# midi-switcher.net
KiCad netlist of a schematic drawn in EAGLE
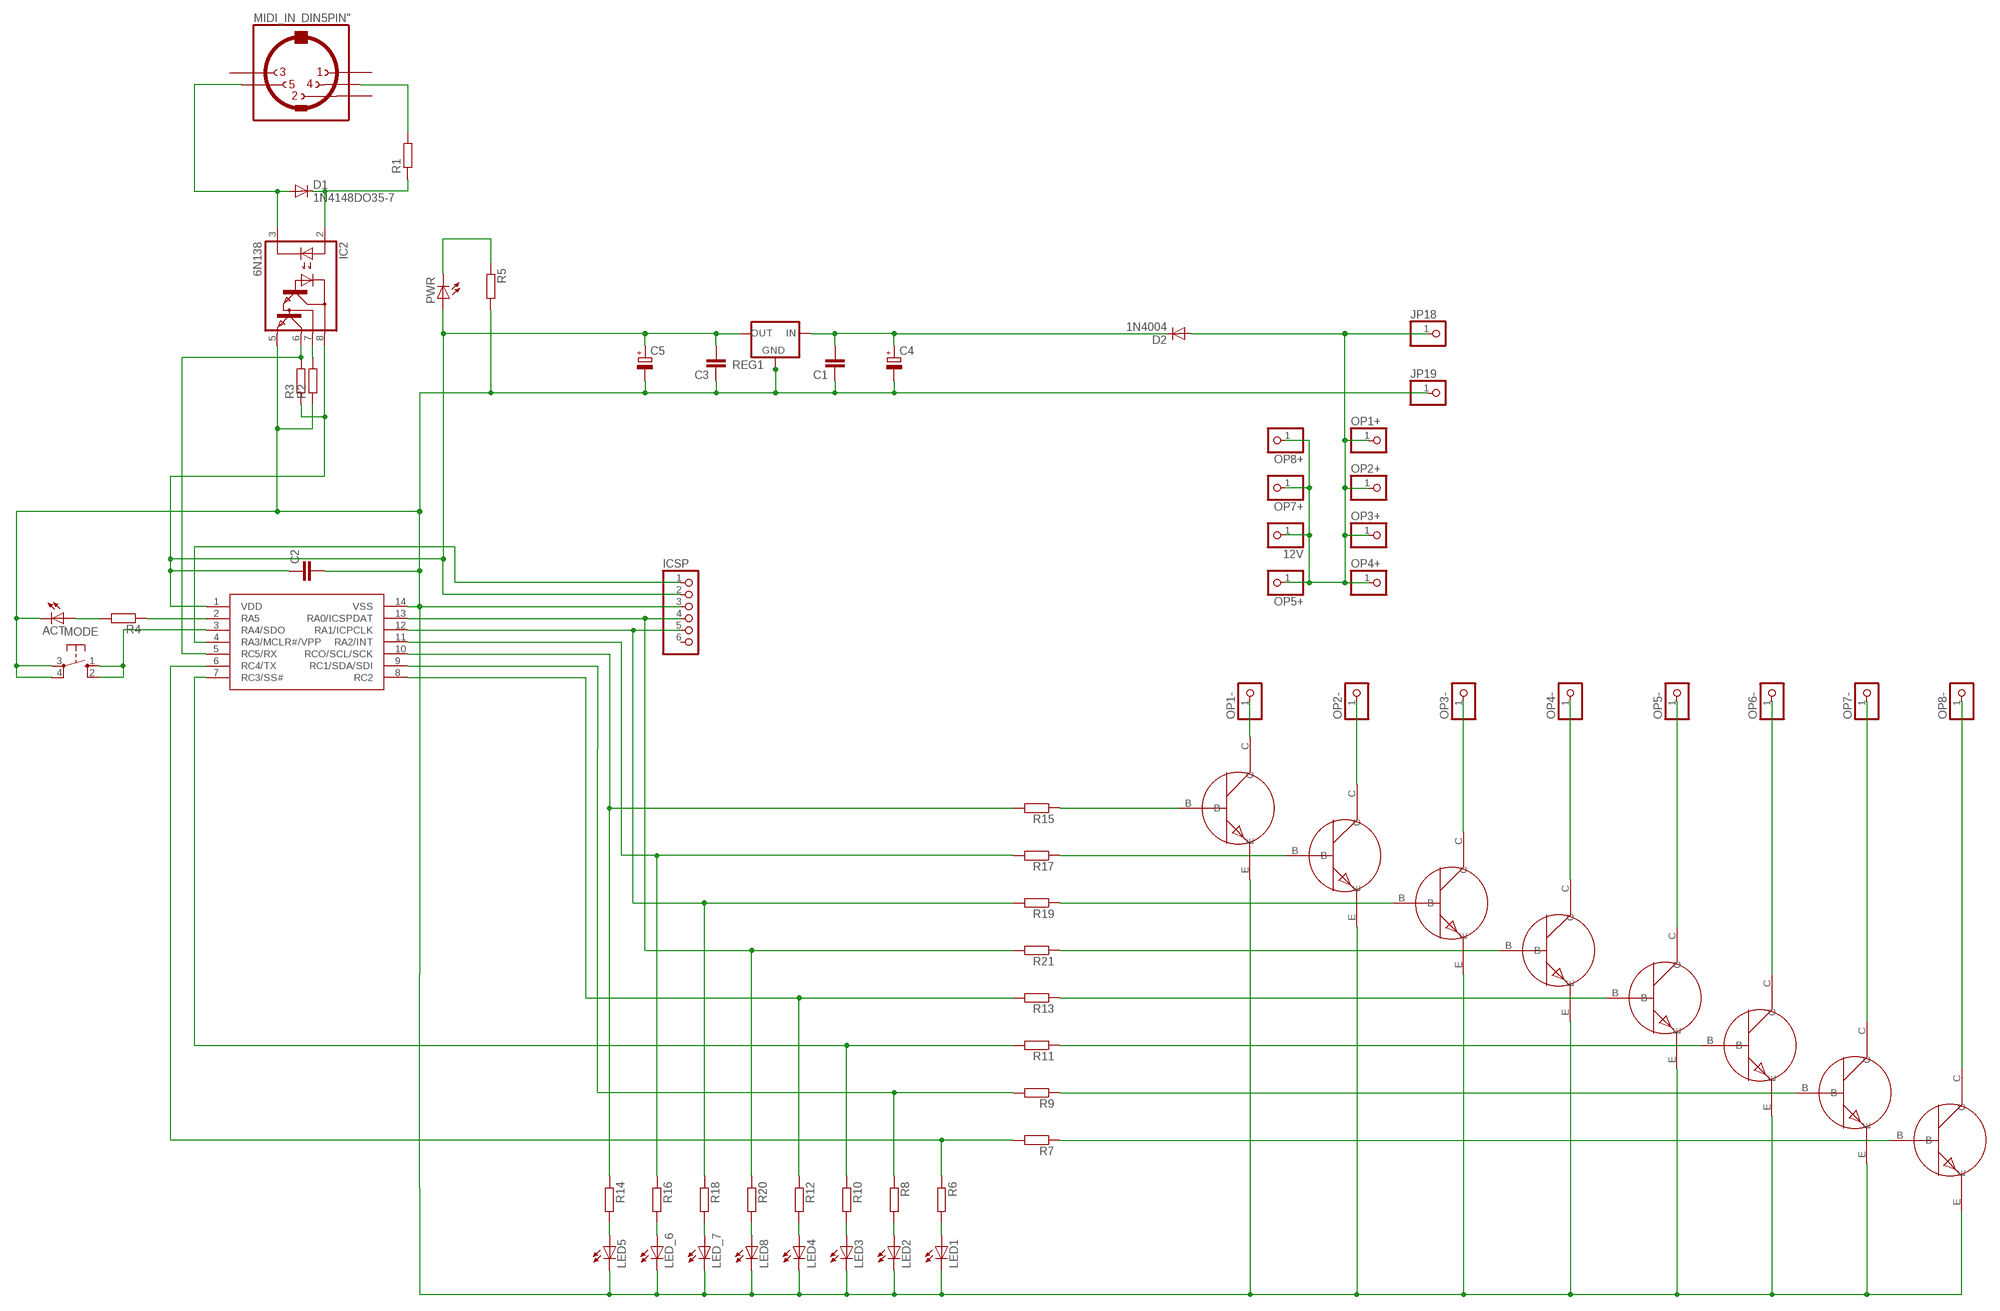
[diagram p0: schematic, sheet 1]

(export (version "E")
  (design (tool "Eeschema 10.0.6"))
  (components
    (comp (ref "12V")
      (value "PINHD-1X1")
      (footprint "eagle-import:1X01")
      (libsource (lib "eagle-import") (part "PINHD-1X1"))
    )
    (comp (ref "ACT")
      (value "LED3MM")
      (footprint "eagle-import:LED3MM")
      (libsource (lib "eagle-import") (part "LED3MM"))
    )
    (comp (ref "C1")
      (value "C-EU025-025X050")
      (footprint "eagle-import:C025-025X050")
      (libsource (lib "eagle-import") (part "C-EU025-025X050"))
    )
    (comp (ref "C2")
      (value "C-EU025-025X050")
      (footprint "eagle-import:C025-025X050")
      (libsource (lib "eagle-import") (part "C-EU025-025X050"))
    )
    (comp (ref "C3")
      (value "C-EU025-025X050")
      (footprint "eagle-import:C025-025X050")
      (libsource (lib "eagle-import") (part "C-EU025-025X050"))
    )
    (comp (ref "C4")
      (value "CPOL-EUE2.5-7")
      (footprint "eagle-import:E2,5-7")
      (libsource (lib "eagle-import") (part "CPOL-EUE2.5-7"))
    )
    (comp (ref "C5")
      (value "CPOL-EUE2.5-7")
      (footprint "eagle-import:E2,5-7")
      (libsource (lib "eagle-import") (part "CPOL-EUE2.5-7"))
    )
    (comp (ref "D1")
      (value "1N4148DO35-7")
      (footprint "eagle-import:DO35-7")
      (libsource (lib "eagle-import") (part "1N4148DO35-7"))
    )
    (comp (ref "D2")
      (value "1N4004")
      (footprint "eagle-import:DO41-10")
      (libsource (lib "eagle-import") (part "1N4004"))
    )
    (comp (ref "IC1")
      (value "PIC16F1825DIL14")
      (footprint "eagle-import:DIL14")
      (libsource (lib "eagle-import") (part "PIC16F1825DIL14"))
    )
    (comp (ref "IC2")
      (value "6N138")
      (footprint "eagle-import:DIL08")
      (libsource (lib "eagle-import") (part "6N138"))
    )
    (comp (ref "ICSP")
      (value "HEADER-1X6")
      (footprint "eagle-import:1X06_OVAL")
      (libsource (lib "eagle-import") (part "HEADER-1X6"))
    )
    (comp (ref "JP18")
      (value "PINHD-1X1")
      (footprint "eagle-import:1X01")
      (libsource (lib "eagle-import") (part "PINHD-1X1"))
    )
    (comp (ref "JP19")
      (value "PINHD-1X1")
      (footprint "eagle-import:1X01")
      (libsource (lib "eagle-import") (part "PINHD-1X1"))
    )
    (comp (ref "LED1")
      (value "LED3MM")
      (footprint "eagle-import:LED3MM")
      (libsource (lib "eagle-import") (part "LED3MM"))
    )
    (comp (ref "LED2")
      (value "LED3MM")
      (footprint "eagle-import:LED3MM")
      (libsource (lib "eagle-import") (part "LED3MM"))
    )
    (comp (ref "LED3")
      (value "LED3MM")
      (footprint "eagle-import:LED3MM")
      (libsource (lib "eagle-import") (part "LED3MM"))
    )
    (comp (ref "LED4")
      (value "LED3MM")
      (footprint "eagle-import:LED3MM")
      (libsource (lib "eagle-import") (part "LED3MM"))
    )
    (comp (ref "LED5")
      (value "LED3MM")
      (footprint "eagle-import:LED3MM")
      (libsource (lib "eagle-import") (part "LED3MM"))
    )
    (comp (ref "LED8")
      (value "LED3MM")
      (footprint "eagle-import:LED3MM")
      (libsource (lib "eagle-import") (part "LED3MM"))
    )
    (comp (ref "LED_6")
      (value "LED3MM")
      (footprint "eagle-import:LED3MM")
      (libsource (lib "eagle-import") (part "LED3MM"))
    )
    (comp (ref "LED_7")
      (value "LED3MM")
      (footprint "eagle-import:LED3MM")
      (libsource (lib "eagle-import") (part "LED3MM"))
    )
    (comp (ref "MIDI_IN")
      (value "DIN5PIN\"")
      (footprint "eagle-import:TRUCONN90")
      (libsource (lib "eagle-import") (part "DIN5PIN{dblquote}"))
    )
    (comp (ref "MODE")
      (value "10-XX")
      (footprint "eagle-import:B3F-10XX")
      (libsource (lib "eagle-import") (part "10-XX"))
    )
    (comp (ref "OP1+")
      (value "PINHD-1X1")
      (footprint "eagle-import:1X01")
      (libsource (lib "eagle-import") (part "PINHD-1X1"))
    )
    (comp (ref "OP1-")
      (value "PINHD-1X1")
      (footprint "eagle-import:1X01")
      (libsource (lib "eagle-import") (part "PINHD-1X1"))
    )
    (comp (ref "OP2+")
      (value "PINHD-1X1")
      (footprint "eagle-import:1X01")
      (libsource (lib "eagle-import") (part "PINHD-1X1"))
    )
    (comp (ref "OP2-")
      (value "PINHD-1X1")
      (footprint "eagle-import:1X01")
      (libsource (lib "eagle-import") (part "PINHD-1X1"))
    )
    (comp (ref "OP3+")
      (value "PINHD-1X1")
      (footprint "eagle-import:1X01")
      (libsource (lib "eagle-import") (part "PINHD-1X1"))
    )
    (comp (ref "OP3-")
      (value "PINHD-1X1")
      (footprint "eagle-import:1X01")
      (libsource (lib "eagle-import") (part "PINHD-1X1"))
    )
    (comp (ref "OP4+")
      (value "PINHD-1X1")
      (footprint "eagle-import:1X01")
      (libsource (lib "eagle-import") (part "PINHD-1X1"))
    )
    (comp (ref "OP4-")
      (value "PINHD-1X1")
      (footprint "eagle-import:1X01")
      (libsource (lib "eagle-import") (part "PINHD-1X1"))
    )
    (comp (ref "OP5+")
      (value "PINHD-1X1")
      (footprint "eagle-import:1X01")
      (libsource (lib "eagle-import") (part "PINHD-1X1"))
    )
    (comp (ref "OP5-")
      (value "PINHD-1X1")
      (footprint "eagle-import:1X01")
      (libsource (lib "eagle-import") (part "PINHD-1X1"))
    )
    (comp (ref "OP6-")
      (value "PINHD-1X1")
      (footprint "eagle-import:1X01")
      (libsource (lib "eagle-import") (part "PINHD-1X1"))
    )
    (comp (ref "OP7+")
      (value "PINHD-1X1")
      (footprint "eagle-import:1X01")
      (libsource (lib "eagle-import") (part "PINHD-1X1"))
    )
    (comp (ref "OP7-")
      (value "PINHD-1X1")
      (footprint "eagle-import:1X01")
      (libsource (lib "eagle-import") (part "PINHD-1X1"))
    )
    (comp (ref "OP8+")
      (value "PINHD-1X1")
      (footprint "eagle-import:1X01")
      (libsource (lib "eagle-import") (part "PINHD-1X1"))
    )
    (comp (ref "OP8-")
      (value "PINHD-1X1")
      (footprint "eagle-import:1X01")
      (libsource (lib "eagle-import") (part "PINHD-1X1"))
    )
    (comp (ref "PWR")
      (value "LED3MM")
      (footprint "eagle-import:LED3MM")
      (libsource (lib "eagle-import") (part "LED3MM"))
    )
    (comp (ref "R1")
      (value "R-EU_0207/7")
      (footprint "eagle-import:0207_7")
      (libsource (lib "eagle-import") (part "R-EU_0207/7"))
    )
    (comp (ref "R2")
      (value "R-EU_0207/7")
      (footprint "eagle-import:0207_7")
      (libsource (lib "eagle-import") (part "R-EU_0207/7"))
    )
    (comp (ref "R3")
      (value "R-EU_0207/7")
      (footprint "eagle-import:0207_7")
      (libsource (lib "eagle-import") (part "R-EU_0207/7"))
    )
    (comp (ref "R4")
      (value "R-EU_0207/7")
      (footprint "eagle-import:0207_7")
      (libsource (lib "eagle-import") (part "R-EU_0207/7"))
    )
    (comp (ref "R5")
      (value "R-EU_0207/7")
      (footprint "eagle-import:0207_7")
      (libsource (lib "eagle-import") (part "R-EU_0207/7"))
    )
    (comp (ref "R6")
      (value "R-EU_0207/7")
      (footprint "eagle-import:0207_7")
      (libsource (lib "eagle-import") (part "R-EU_0207/7"))
    )
    (comp (ref "R7")
      (value "R-EU_0207/7")
      (footprint "eagle-import:0207_7")
      (libsource (lib "eagle-import") (part "R-EU_0207/7"))
    )
    (comp (ref "R8")
      (value "R-EU_0207/7")
      (footprint "eagle-import:0207_7")
      (libsource (lib "eagle-import") (part "R-EU_0207/7"))
    )
    (comp (ref "R9")
      (value "R-EU_0207/7")
      (footprint "eagle-import:0207_7")
      (libsource (lib "eagle-import") (part "R-EU_0207/7"))
    )
    (comp (ref "R10")
      (value "R-EU_0207/7")
      (footprint "eagle-import:0207_7")
      (libsource (lib "eagle-import") (part "R-EU_0207/7"))
    )
    (comp (ref "R11")
      (value "R-EU_0207/7")
      (footprint "eagle-import:0207_7")
      (libsource (lib "eagle-import") (part "R-EU_0207/7"))
    )
    (comp (ref "R12")
      (value "R-EU_0207/7")
      (footprint "eagle-import:0207_7")
      (libsource (lib "eagle-import") (part "R-EU_0207/7"))
    )
    (comp (ref "R13")
      (value "R-EU_0207/7")
      (footprint "eagle-import:0207_7")
      (libsource (lib "eagle-import") (part "R-EU_0207/7"))
    )
    (comp (ref "R14")
      (value "R-EU_0207/7")
      (footprint "eagle-import:0207_7")
      (libsource (lib "eagle-import") (part "R-EU_0207/7"))
    )
    (comp (ref "R15")
      (value "R-EU_0207/7")
      (footprint "eagle-import:0207_7")
      (libsource (lib "eagle-import") (part "R-EU_0207/7"))
    )
    (comp (ref "R16")
      (value "R-EU_0207/7")
      (footprint "eagle-import:0207_7")
      (libsource (lib "eagle-import") (part "R-EU_0207/7"))
    )
    (comp (ref "R17")
      (value "R-EU_0207/7")
      (footprint "eagle-import:0207_7")
      (libsource (lib "eagle-import") (part "R-EU_0207/7"))
    )
    (comp (ref "R18")
      (value "R-EU_0207/7")
      (footprint "eagle-import:0207_7")
      (libsource (lib "eagle-import") (part "R-EU_0207/7"))
    )
    (comp (ref "R19")
      (value "R-EU_0207/7")
      (footprint "eagle-import:0207_7")
      (libsource (lib "eagle-import") (part "R-EU_0207/7"))
    )
    (comp (ref "R20")
      (value "R-EU_0207/7")
      (footprint "eagle-import:0207_7")
      (libsource (lib "eagle-import") (part "R-EU_0207/7"))
    )
    (comp (ref "R21")
      (value "R-EU_0207/7")
      (footprint "eagle-import:0207_7")
      (libsource (lib "eagle-import") (part "R-EU_0207/7"))
    )
    (comp (ref "REG1")
      (value "78XXS")
      (footprint "eagle-import:78XXS")
      (libsource (lib "eagle-import") (part "78XXS"))
    )
    (comp (ref "U$1")
      (value "TIP120")
      (footprint "eagle-import:TIP120")
      (libsource (lib "eagle-import") (part "TIP120"))
    )
    (comp (ref "U$2")
      (value "TIP120")
      (footprint "eagle-import:TIP120")
      (libsource (lib "eagle-import") (part "TIP120"))
    )
    (comp (ref "U$3")
      (value "TIP120")
      (footprint "eagle-import:TIP120")
      (libsource (lib "eagle-import") (part "TIP120"))
    )
    (comp (ref "U$4")
      (value "TIP120")
      (footprint "eagle-import:TIP120")
      (libsource (lib "eagle-import") (part "TIP120"))
    )
    (comp (ref "U$5")
      (value "TIP120")
      (footprint "eagle-import:TIP120")
      (libsource (lib "eagle-import") (part "TIP120"))
    )
    (comp (ref "U$6")
      (value "TIP120")
      (footprint "eagle-import:TIP120")
      (libsource (lib "eagle-import") (part "TIP120"))
    )
    (comp (ref "U$7")
      (value "TIP120")
      (footprint "eagle-import:TIP120")
      (libsource (lib "eagle-import") (part "TIP120"))
    )
    (comp (ref "U$8")
      (value "TIP120")
      (footprint "eagle-import:TIP120")
      (libsource (lib "eagle-import") (part "TIP120"))
    )
  )
  (nets
    (net (code "1") (name "Net-(12V-Pad1)") (class "Default")
      (node (ref "12V") (pin "1") (pinfunction "1_1") (pintype "passive"))
      (node (ref "D2") (pin "A") (pinfunction "A_A") (pintype "passive"))
      (node (ref "JP18") (pin "1") (pinfunction "1_1") (pintype "passive"))
      (node (ref "OP1+") (pin "1") (pinfunction "1_1") (pintype "passive"))
      (node (ref "OP2+") (pin "1") (pinfunction "1_1") (pintype "passive"))
      (node (ref "OP3+") (pin "1") (pinfunction "1_1") (pintype "passive"))
      (node (ref "OP4+") (pin "1") (pinfunction "1_1") (pintype "passive"))
      (node (ref "OP5+") (pin "1") (pinfunction "1_1") (pintype "passive"))
      (node (ref "OP7+") (pin "1") (pinfunction "1_1") (pintype "passive"))
      (node (ref "OP8+") (pin "1") (pinfunction "1_1") (pintype "passive"))
    )
    (net (code "2") (name "Net-(ACT-C)") (class "Default")
      (node (ref "ACT") (pin "K") (pinfunction "C_K") (pintype "passive"))
      (node (ref "C1") (pin "1") (pinfunction "1_1") (pintype "passive"))
      (node (ref "C2") (pin "2") (pinfunction "2_2") (pintype "passive"))
      (node (ref "C3") (pin "1") (pinfunction "1_1") (pintype "passive"))
      (node (ref "C4") (pin "-") (pinfunction "-_-") (pintype "passive"))
      (node (ref "C5") (pin "-") (pinfunction "-_-") (pintype "passive"))
      (node (ref "IC1") (pin "14") (pinfunction "VSS_14") (pintype "power_in"))
      (node (ref "IC2") (pin "5") (pinfunction "GND_5") (pintype "passive"))
      (node (ref "ICSP") (pin "3") (pinfunction "3_3") (pintype "passive"))
      (node (ref "JP19") (pin "1") (pinfunction "1_1") (pintype "passive"))
      (node (ref "LED1") (pin "K") (pinfunction "C_K") (pintype "passive"))
      (node (ref "LED2") (pin "K") (pinfunction "C_K") (pintype "passive"))
      (node (ref "LED3") (pin "K") (pinfunction "C_K") (pintype "passive"))
      (node (ref "LED4") (pin "K") (pinfunction "C_K") (pintype "passive"))
      (node (ref "LED5") (pin "K") (pinfunction "C_K") (pintype "passive"))
      (node (ref "LED8") (pin "K") (pinfunction "C_K") (pintype "passive"))
      (node (ref "LED_6") (pin "K") (pinfunction "C_K") (pintype "passive"))
      (node (ref "LED_7") (pin "K") (pinfunction "C_K") (pintype "passive"))
      (node (ref "MODE") (pin "3") (pinfunction "P_3") (pintype "passive"))
      (node (ref "MODE") (pin "4") (pinfunction "P1_4") (pintype "passive"))
      (node (ref "R2") (pin "1") (pinfunction "1_1") (pintype "passive"))
      (node (ref "R5") (pin "2") (pinfunction "2_2") (pintype "passive"))
      (node (ref "REG1") (pin "GND") (pinfunction "GND_GND") (pintype "input"))
      (node (ref "U$1") (pin "E") (pinfunction "E_E") (pintype "bidirectional"))
      (node (ref "U$2") (pin "E") (pinfunction "E_E") (pintype "bidirectional"))
      (node (ref "U$3") (pin "E") (pinfunction "E_E") (pintype "bidirectional"))
      (node (ref "U$4") (pin "E") (pinfunction "E_E") (pintype "bidirectional"))
      (node (ref "U$5") (pin "E") (pinfunction "E_E") (pintype "bidirectional"))
      (node (ref "U$6") (pin "E") (pinfunction "E_E") (pintype "bidirectional"))
      (node (ref "U$7") (pin "E") (pinfunction "E_E") (pintype "bidirectional"))
      (node (ref "U$8") (pin "E") (pinfunction "E_E") (pintype "bidirectional"))
    )
    (net (code "3") (name "Net-(ACT-PadA)") (class "Default")
      (node (ref "ACT") (pin "A") (pinfunction "A_A") (pintype "passive"))
      (node (ref "R4") (pin "2") (pinfunction "2_2") (pintype "passive"))
    )
    (net (code "4") (name "Net-(C1-Pad2)") (class "Default")
      (node (ref "C1") (pin "2") (pinfunction "2_2") (pintype "passive"))
      (node (ref "C4") (pin "+") (pinfunction "+_+") (pintype "passive"))
      (node (ref "D2") (pin "C") (pinfunction "C_C") (pintype "passive"))
      (node (ref "REG1") (pin "IN") (pinfunction "IN_IN") (pintype "input"))
    )
    (net (code "5") (name "Net-(IC1-RA0{slash}ICSPDAT)") (class "Default")
      (node (ref "IC1") (pin "13") (pinfunction "RA0/ICSPDAT_13") (pintype "bidirectional"))
      (node (ref "ICSP") (pin "4") (pinfunction "4_4") (pintype "passive"))
      (node (ref "R20") (pin "1") (pinfunction "1_1") (pintype "passive"))
      (node (ref "R21") (pin "2") (pinfunction "2_2") (pintype "passive"))
    )
    (net (code "6") (name "Net-(IC1-RA1{slash}ICPCLK)") (class "Default")
      (node (ref "IC1") (pin "12") (pinfunction "RA1/ICPCLK_12") (pintype "bidirectional"))
      (node (ref "ICSP") (pin "5") (pinfunction "5_5") (pintype "passive"))
      (node (ref "R18") (pin "1") (pinfunction "1_1") (pintype "passive"))
      (node (ref "R19") (pin "2") (pinfunction "2_2") (pintype "passive"))
    )
    (net (code "7") (name "Net-(IC1-RA2{slash}INT)") (class "Default")
      (node (ref "IC1") (pin "11") (pinfunction "RA2/INT_11") (pintype "bidirectional"))
      (node (ref "R16") (pin "1") (pinfunction "1_1") (pintype "passive"))
      (node (ref "R17") (pin "2") (pinfunction "2_2") (pintype "passive"))
    )
    (net (code "8") (name "Net-(IC1-RA3{slash}MCLR#{slash}VPP)") (class "Default")
      (node (ref "IC1") (pin "4") (pinfunction "RA3/MCLR#/VPP_4") (pintype "input"))
      (node (ref "ICSP") (pin "1") (pinfunction "1_1") (pintype "passive"))
    )
    (net (code "9") (name "Net-(IC1-RA4{slash}SDO)") (class "Default")
      (node (ref "IC1") (pin "3") (pinfunction "RA4/SDO_3") (pintype "bidirectional"))
      (node (ref "MODE") (pin "1") (pinfunction "S_1") (pintype "passive"))
      (node (ref "MODE") (pin "2") (pinfunction "S1_2") (pintype "passive"))
    )
    (net (code "10") (name "Net-(IC1-RA5)") (class "Default")
      (node (ref "IC1") (pin "2") (pinfunction "RA5_2") (pintype "bidirectional"))
      (node (ref "R4") (pin "1") (pinfunction "1_1") (pintype "passive"))
    )
    (net (code "11") (name "Net-(IC1-RC1{slash}SDA{slash}SDI)") (class "Default")
      (node (ref "IC1") (pin "9") (pinfunction "RC1/SDA/SDI_9") (pintype "bidirectional"))
      (node (ref "R8") (pin "1") (pinfunction "1_1") (pintype "passive"))
      (node (ref "R9") (pin "2") (pinfunction "2_2") (pintype "passive"))
    )
    (net (code "12") (name "Net-(IC1-RC2)") (class "Default")
      (node (ref "IC1") (pin "8") (pinfunction "RC2_8") (pintype "bidirectional"))
      (node (ref "R12") (pin "1") (pinfunction "1_1") (pintype "passive"))
      (node (ref "R13") (pin "2") (pinfunction "2_2") (pintype "passive"))
    )
    (net (code "13") (name "Net-(IC1-RC3{slash}SS#)") (class "Default")
      (node (ref "IC1") (pin "7") (pinfunction "RC3/SS#_7") (pintype "bidirectional"))
      (node (ref "R10") (pin "1") (pinfunction "1_1") (pintype "passive"))
      (node (ref "R11") (pin "2") (pinfunction "2_2") (pintype "passive"))
    )
    (net (code "14") (name "Net-(IC1-RC4{slash}TX)") (class "Default")
      (node (ref "IC1") (pin "6") (pinfunction "RC4/TX_6") (pintype "bidirectional"))
      (node (ref "R6") (pin "1") (pinfunction "1_1") (pintype "passive"))
      (node (ref "R7") (pin "2") (pinfunction "2_2") (pintype "passive"))
    )
    (net (code "15") (name "Net-(IC1-RC5{slash}RX)") (class "Default")
      (node (ref "IC1") (pin "5") (pinfunction "RC5/RX_5") (pintype "bidirectional"))
      (node (ref "IC2") (pin "6") (pinfunction "VO_6") (pintype "passive"))
      (node (ref "R3") (pin "2") (pinfunction "2_2") (pintype "passive"))
    )
    (net (code "16") (name "Net-(IC1-RCO{slash}SCL{slash}SCK)") (class "Default")
      (node (ref "IC1") (pin "10") (pinfunction "RCO/SCL/SCK_10") (pintype "bidirectional"))
      (node (ref "R14") (pin "1") (pinfunction "1_1") (pintype "passive"))
      (node (ref "R15") (pin "2") (pinfunction "2_2") (pintype "passive"))
    )
    (net (code "17") (name "Net-(IC1-VDD)") (class "Default")
      (node (ref "C2") (pin "1") (pinfunction "1_1") (pintype "passive"))
      (node (ref "C3") (pin "2") (pinfunction "2_2") (pintype "passive"))
      (node (ref "C5") (pin "+") (pinfunction "+_+") (pintype "passive"))
      (node (ref "IC1") (pin "1") (pinfunction "VDD_1") (pintype "power_in"))
      (node (ref "IC2") (pin "8") (pinfunction "VCC_8") (pintype "passive"))
      (node (ref "ICSP") (pin "2") (pinfunction "2_2") (pintype "passive"))
      (node (ref "PWR") (pin "A") (pinfunction "A_A") (pintype "passive"))
      (node (ref "R3") (pin "1") (pinfunction "1_1") (pintype "passive"))
      (node (ref "REG1") (pin "OUT") (pinfunction "OUT_OUT") (pintype "passive"))
    )
    (net (code "18") (name "Net-(IC2-A)") (class "Default")
      (node (ref "D1") (pin "C") (pinfunction "C_C") (pintype "passive"))
      (node (ref "IC2") (pin "2") (pinfunction "A_2") (pintype "passive"))
      (node (ref "R1") (pin "1") (pinfunction "1_1") (pintype "passive"))
    )
    (net (code "19") (name "Net-(IC2-C)") (class "Default")
      (node (ref "D1") (pin "A") (pinfunction "A_A") (pintype "passive"))
      (node (ref "IC2") (pin "3") (pinfunction "C_3") (pintype "passive"))
      (node (ref "MIDI_IN") (pin "5") (pinfunction "5_5") (pintype "passive"))
    )
    (net (code "20") (name "Net-(IC2-VB)") (class "Default")
      (node (ref "IC2") (pin "7") (pinfunction "VB_7") (pintype "passive"))
      (node (ref "R2") (pin "2") (pinfunction "2_2") (pintype "passive"))
    )
    (net (code "21") (name "Net-(LED1-PadA)") (class "Default")
      (node (ref "LED1") (pin "A") (pinfunction "A_A") (pintype "passive"))
      (node (ref "R6") (pin "2") (pinfunction "2_2") (pintype "passive"))
    )
    (net (code "22") (name "Net-(LED2-PadA)") (class "Default")
      (node (ref "LED2") (pin "A") (pinfunction "A_A") (pintype "passive"))
      (node (ref "R8") (pin "2") (pinfunction "2_2") (pintype "passive"))
    )
    (net (code "23") (name "Net-(LED3-PadA)") (class "Default")
      (node (ref "LED3") (pin "A") (pinfunction "A_A") (pintype "passive"))
      (node (ref "R10") (pin "2") (pinfunction "2_2") (pintype "passive"))
    )
    (net (code "24") (name "Net-(LED4-PadA)") (class "Default")
      (node (ref "LED4") (pin "A") (pinfunction "A_A") (pintype "passive"))
      (node (ref "R12") (pin "2") (pinfunction "2_2") (pintype "passive"))
    )
    (net (code "25") (name "Net-(LED5-PadA)") (class "Default")
      (node (ref "LED5") (pin "A") (pinfunction "A_A") (pintype "passive"))
      (node (ref "R14") (pin "2") (pinfunction "2_2") (pintype "passive"))
    )
    (net (code "26") (name "Net-(LED8-PadA)") (class "Default")
      (node (ref "LED8") (pin "A") (pinfunction "A_A") (pintype "passive"))
      (node (ref "R20") (pin "2") (pinfunction "2_2") (pintype "passive"))
    )
    (net (code "27") (name "Net-(LED_6-PadA)") (class "Default")
      (node (ref "LED_6") (pin "A") (pinfunction "A_A") (pintype "passive"))
      (node (ref "R16") (pin "2") (pinfunction "2_2") (pintype "passive"))
    )
    (net (code "28") (name "Net-(LED_7-PadA)") (class "Default")
      (node (ref "LED_7") (pin "A") (pinfunction "A_A") (pintype "passive"))
      (node (ref "R18") (pin "2") (pinfunction "2_2") (pintype "passive"))
    )
    (net (code "29") (name "Net-(MIDI_IN-Pad4)") (class "Default")
      (node (ref "MIDI_IN") (pin "4") (pinfunction "4_4") (pintype "passive"))
      (node (ref "R1") (pin "2") (pinfunction "2_2") (pintype "passive"))
    )
    (net (code "30") (name "Net-(OP1--Pad1)") (class "Default")
      (node (ref "OP1-") (pin "1") (pinfunction "1_1") (pintype "passive"))
      (node (ref "U$1") (pin "C") (pinfunction "C_C") (pintype "bidirectional"))
    )
    (net (code "31") (name "Net-(OP2--Pad1)") (class "Default")
      (node (ref "OP2-") (pin "1") (pinfunction "1_1") (pintype "passive"))
      (node (ref "U$2") (pin "C") (pinfunction "C_C") (pintype "bidirectional"))
    )
    (net (code "32") (name "Net-(OP3--Pad1)") (class "Default")
      (node (ref "OP3-") (pin "1") (pinfunction "1_1") (pintype "passive"))
      (node (ref "U$4") (pin "C") (pinfunction "C_C") (pintype "bidirectional"))
    )
    (net (code "33") (name "Net-(OP4--Pad1)") (class "Default")
      (node (ref "OP4-") (pin "1") (pinfunction "1_1") (pintype "passive"))
      (node (ref "U$3") (pin "C") (pinfunction "C_C") (pintype "bidirectional"))
    )
    (net (code "34") (name "Net-(OP5--Pad1)") (class "Default")
      (node (ref "OP5-") (pin "1") (pinfunction "1_1") (pintype "passive"))
      (node (ref "U$5") (pin "C") (pinfunction "C_C") (pintype "bidirectional"))
    )
    (net (code "35") (name "Net-(OP6--Pad1)") (class "Default")
      (node (ref "OP6-") (pin "1") (pinfunction "1_1") (pintype "passive"))
      (node (ref "U$6") (pin "C") (pinfunction "C_C") (pintype "bidirectional"))
    )
    (net (code "36") (name "Net-(OP7--Pad1)") (class "Default")
      (node (ref "OP7-") (pin "1") (pinfunction "1_1") (pintype "passive"))
      (node (ref "U$7") (pin "C") (pinfunction "C_C") (pintype "bidirectional"))
    )
    (net (code "37") (name "Net-(OP8--Pad1)") (class "Default")
      (node (ref "OP8-") (pin "1") (pinfunction "1_1") (pintype "passive"))
      (node (ref "U$8") (pin "C") (pinfunction "C_C") (pintype "bidirectional"))
    )
    (net (code "38") (name "Net-(PWR-C)") (class "Default")
      (node (ref "PWR") (pin "K") (pinfunction "C_K") (pintype "passive"))
      (node (ref "R5") (pin "1") (pinfunction "1_1") (pintype "passive"))
    )
    (net (code "39") (name "Net-(R7-Pad1)") (class "Default")
      (node (ref "R7") (pin "1") (pinfunction "1_1") (pintype "passive"))
      (node (ref "U$8") (pin "B") (pinfunction "B_B") (pintype "bidirectional"))
    )
    (net (code "40") (name "Net-(R9-Pad1)") (class "Default")
      (node (ref "R9") (pin "1") (pinfunction "1_1") (pintype "passive"))
      (node (ref "U$7") (pin "B") (pinfunction "B_B") (pintype "bidirectional"))
    )
    (net (code "41") (name "Net-(R11-Pad1)") (class "Default")
      (node (ref "R11") (pin "1") (pinfunction "1_1") (pintype "passive"))
      (node (ref "U$6") (pin "B") (pinfunction "B_B") (pintype "bidirectional"))
    )
    (net (code "42") (name "Net-(R13-Pad1)") (class "Default")
      (node (ref "R13") (pin "1") (pinfunction "1_1") (pintype "passive"))
      (node (ref "U$5") (pin "B") (pinfunction "B_B") (pintype "bidirectional"))
    )
    (net (code "43") (name "Net-(R15-Pad1)") (class "Default")
      (node (ref "R15") (pin "1") (pinfunction "1_1") (pintype "passive"))
      (node (ref "U$1") (pin "B") (pinfunction "B_B") (pintype "bidirectional"))
    )
    (net (code "44") (name "Net-(R17-Pad1)") (class "Default")
      (node (ref "R17") (pin "1") (pinfunction "1_1") (pintype "passive"))
      (node (ref "U$2") (pin "B") (pinfunction "B_B") (pintype "bidirectional"))
    )
    (net (code "45") (name "Net-(R19-Pad1)") (class "Default")
      (node (ref "R19") (pin "1") (pinfunction "1_1") (pintype "passive"))
      (node (ref "U$4") (pin "B") (pinfunction "B_B") (pintype "bidirectional"))
    )
    (net (code "46") (name "Net-(R21-Pad1)") (class "Default")
      (node (ref "R21") (pin "1") (pinfunction "1_1") (pintype "passive"))
      (node (ref "U$3") (pin "B") (pinfunction "B_B") (pintype "bidirectional"))
    )
    (net (code "47") (name "unconnected-(ICSP-Pad6)") (class "Default")
      (node (ref "ICSP") (pin "6") (pinfunction "6_6") (pintype "passive"))
    )
    (net (code "48") (name "unconnected-(MIDI_IN-Pad1)") (class "Default")
      (node (ref "MIDI_IN") (pin "1") (pinfunction "1_1") (pintype "passive"))
    )
    (net (code "49") (name "unconnected-(MIDI_IN-Pad2)") (class "Default")
      (node (ref "MIDI_IN") (pin "2") (pinfunction "2_2") (pintype "passive"))
    )
    (net (code "50") (name "unconnected-(MIDI_IN-Pad3)") (class "Default")
      (node (ref "MIDI_IN") (pin "3") (pinfunction "3_3") (pintype "passive"))
    )
  )
)
